# untitled.net
KiCad netlist of a schematic drawn in EAGLE
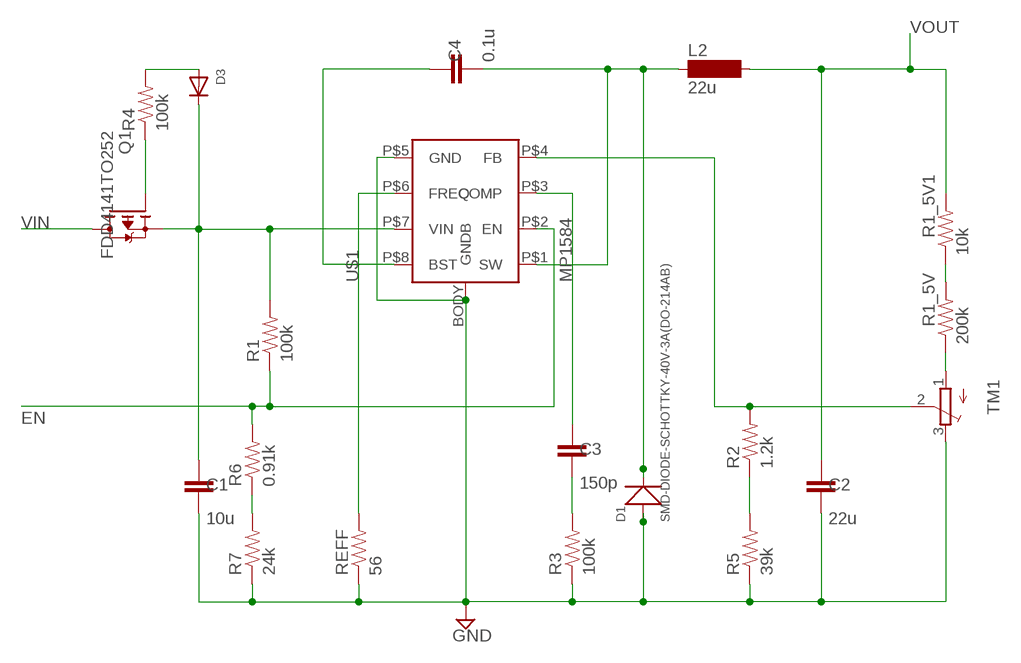
[diagram p0: schematic, sheet 1]

(export (version "E")
  (design (tool "Eeschema 10.0.6"))
  (components
    (comp (ref "C1")
      (value "10u")
      (footprint "eagle-import:0603-CAP")
      (libsource (lib "eagle-import") (part "CAP0603-CAP"))
    )
    (comp (ref "C2")
      (value "22u")
      (footprint "eagle-import:0603-CAP")
      (libsource (lib "eagle-import") (part "CAP0603-CAP"))
    )
    (comp (ref "C3")
      (value "150p")
      (footprint "eagle-import:0603-CAP")
      (libsource (lib "eagle-import") (part "CAP0603-CAP"))
    )
    (comp (ref "C4")
      (value "0.1u")
      (footprint "eagle-import:0603-CAP")
      (libsource (lib "eagle-import") (part "CAP0603-CAP"))
    )
    (comp (ref "D1")
      (value "SMD-DIODE-SCHOTTKY-40V-3A(DO-214AB)")
      (footprint "eagle-import:DO-214AB")
      (fields (field (name "MF") "Vishay") (field (name "MP") "SS34-E3/57T"))
      (libsource (lib "eagle-import") (part "SMD-DIODE-SCHOTTKY-40V-3A(DO-214AB)"))
    )
    (comp (ref "D3")
      (value "DIODESOD-523")
      (footprint "eagle-import:SOD-523")
      (libsource (lib "eagle-import") (part "DIODESOD-523"))
    )
    (comp (ref "L2")
      (value "22u")
      (footprint "eagle-import:SM-NE45")
      (libsource (lib "eagle-import") (part "SM-NE45"))
    )
    (comp (ref "Q1")
      (value "FDD4141TO252")
      (footprint "eagle-import:TO252")
      (libsource (lib "eagle-import") (part "FDD4141TO252"))
    )
    (comp (ref "R1")
      (value "100k")
      (footprint "eagle-import:0603-RES")
      (libsource (lib "eagle-import") (part "RESISTOR0603-RES"))
    )
    (comp (ref "R1_5V")
      (value "200k")
      (footprint "eagle-import:0603-RES")
      (libsource (lib "eagle-import") (part "RESISTOR0603-RES"))
    )
    (comp (ref "R1_5V1")
      (value "10k")
      (footprint "eagle-import:0603-RES")
      (libsource (lib "eagle-import") (part "RESISTOR0603-RES"))
    )
    (comp (ref "R2")
      (value "1.2k")
      (footprint "eagle-import:0603-RES")
      (libsource (lib "eagle-import") (part "RESISTOR0603-RES"))
    )
    (comp (ref "R3")
      (value "100k")
      (footprint "eagle-import:0603-RES")
      (libsource (lib "eagle-import") (part "RESISTOR0603"))
    )
    (comp (ref "R4")
      (value "100k")
      (footprint "eagle-import:0603-RES")
      (libsource (lib "eagle-import") (part "RESISTOR0603-RES"))
    )
    (comp (ref "R5")
      (value "39k")
      (footprint "eagle-import:0603-RES")
      (libsource (lib "eagle-import") (part "RESISTOR0603"))
    )
    (comp (ref "R6")
      (value "0.91k")
      (footprint "eagle-import:0603-RES")
      (libsource (lib "eagle-import") (part "RESISTOR0603"))
    )
    (comp (ref "R7")
      (value "24k")
      (footprint "eagle-import:0603-RES")
      (libsource (lib "eagle-import") (part "RESISTOR0603-RES"))
    )
    (comp (ref "REFF")
      (value "56")
      (footprint "eagle-import:0603-RES")
      (libsource (lib "eagle-import") (part "RESISTOR0603-RES"))
    )
    (comp (ref "TM1")
      (value "TRIMPOTTC33X")
      (footprint "eagle-import:TC33X")
      (libsource (lib "eagle-import") (part "TRIMPOTTC33X"))
    )
    (comp (ref "U$1")
      (value "MP1584")
      (footprint "eagle-import:MP")
      (libsource (lib "eagle-import") (part "MP1584"))
    )
  )
  (nets
    (net (code "1") (name "/EN") (class "Default")
      (node (ref "R1") (pin "1") (pinfunction "1_1") (pintype "passive"))
      (node (ref "R6") (pin "2") (pinfunction "2_2") (pintype "passive"))
      (node (ref "U$1") (pin "P$2") (pinfunction "EN_P$2") (pintype "bidirectional"))
    )
    (net (code "2") (name "/VIN") (class "Default")
      (node (ref "Q1") (pin "3") (pinfunction "D_3") (pintype "passive"))
    )
    (net (code "3") (name "/VOUT") (class "Default")
      (node (ref "C2") (pin "1") (pinfunction "1_1") (pintype "passive"))
      (node (ref "L2") (pin "2") (pinfunction "2_2") (pintype "passive"))
      (node (ref "R1_5V1") (pin "2") (pinfunction "2_2") (pintype "passive"))
    )
    (net (code "4") (name "GND") (class "Default")
      (node (ref "C1") (pin "2") (pinfunction "2_2") (pintype "passive"))
      (node (ref "C2") (pin "2") (pinfunction "2_2") (pintype "passive"))
      (node (ref "D1") (pin "1") (pinfunction "+_1") (pintype "passive"))
      (node (ref "R3") (pin "1") (pinfunction "1_1") (pintype "passive"))
      (node (ref "R5") (pin "1") (pinfunction "1_1") (pintype "passive"))
      (node (ref "R7") (pin "1") (pinfunction "1_1") (pintype "passive"))
      (node (ref "REFF") (pin "1") (pinfunction "1_1") (pintype "passive"))
      (node (ref "TM1") (pin "3") (pinfunction "E_3") (pintype "passive"))
      (node (ref "U$1") (pin "BODY") (pinfunction "GNDB_BODY") (pintype "bidirectional"))
      (node (ref "U$1") (pin "P$5") (pinfunction "GND_P$5") (pintype "bidirectional"))
    )
    (net (code "5") (name "Net-(C3-Pad2)") (class "Default")
      (node (ref "C3") (pin "2") (pinfunction "2_2") (pintype "passive"))
      (node (ref "R3") (pin "2") (pinfunction "2_2") (pintype "passive"))
    )
    (net (code "6") (name "Net-(D1--)") (class "Default")
      (node (ref "C4") (pin "2") (pinfunction "2_2") (pintype "passive"))
      (node (ref "D1") (pin "2") (pinfunction "-_2") (pintype "passive"))
      (node (ref "L2") (pin "1") (pinfunction "1_1") (pintype "passive"))
      (node (ref "U$1") (pin "P$1") (pinfunction "SW_P$1") (pintype "bidirectional"))
    )
    (net (code "7") (name "Net-(D3-C)") (class "Default")
      (node (ref "C1") (pin "1") (pinfunction "1_1") (pintype "passive"))
      (node (ref "D3") (pin "K") (pinfunction "C_K") (pintype "passive"))
      (node (ref "Q1") (pin "2") (pinfunction "S_2") (pintype "passive"))
      (node (ref "R1") (pin "2") (pinfunction "2_2") (pintype "passive"))
      (node (ref "U$1") (pin "P$7") (pinfunction "VIN_P$7") (pintype "bidirectional"))
    )
    (net (code "8") (name "Net-(D3-PadA)") (class "Default")
      (node (ref "D3") (pin "A") (pinfunction "A_A") (pintype "passive"))
      (node (ref "R4") (pin "2") (pinfunction "2_2") (pintype "passive"))
    )
    (net (code "9") (name "Net-(Q1-G)") (class "Default")
      (node (ref "Q1") (pin "1") (pinfunction "G_1") (pintype "passive"))
      (node (ref "R4") (pin "1") (pinfunction "1_1") (pintype "passive"))
    )
    (net (code "10") (name "Net-(R1_5V-Pad2)") (class "Default")
      (node (ref "R1_5V") (pin "2") (pinfunction "2_2") (pintype "passive"))
      (node (ref "R1_5V1") (pin "1") (pinfunction "1_1") (pintype "passive"))
    )
    (net (code "11") (name "Net-(R2-Pad1)") (class "Default")
      (node (ref "R2") (pin "1") (pinfunction "1_1") (pintype "passive"))
      (node (ref "R5") (pin "2") (pinfunction "2_2") (pintype "passive"))
    )
    (net (code "12") (name "Net-(R6-Pad1)") (class "Default")
      (node (ref "R6") (pin "1") (pinfunction "1_1") (pintype "passive"))
      (node (ref "R7") (pin "2") (pinfunction "2_2") (pintype "passive"))
    )
    (net (code "13") (name "Net-(TM1-A)") (class "Default")
      (node (ref "R1_5V") (pin "1") (pinfunction "1_1") (pintype "passive"))
      (node (ref "TM1") (pin "1") (pinfunction "A_1") (pintype "passive"))
    )
    (net (code "14") (name "Net-(TM1-S)") (class "Default")
      (node (ref "R2") (pin "2") (pinfunction "2_2") (pintype "passive"))
      (node (ref "TM1") (pin "2") (pinfunction "S_2") (pintype "passive"))
      (node (ref "U$1") (pin "P$4") (pinfunction "FB_P$4") (pintype "bidirectional"))
    )
    (net (code "15") (name "Net-(U$1-BST)") (class "Default")
      (node (ref "C4") (pin "1") (pinfunction "1_1") (pintype "passive"))
      (node (ref "U$1") (pin "P$8") (pinfunction "BST_P$8") (pintype "bidirectional"))
    )
    (net (code "16") (name "Net-(U$1-COMP)") (class "Default")
      (node (ref "C3") (pin "1") (pinfunction "1_1") (pintype "passive"))
      (node (ref "U$1") (pin "P$3") (pinfunction "COMP_P$3") (pintype "bidirectional"))
    )
    (net (code "17") (name "Net-(U$1-FREQ)") (class "Default")
      (node (ref "REFF") (pin "2") (pinfunction "2_2") (pintype "passive"))
      (node (ref "U$1") (pin "P$6") (pinfunction "FREQ_P$6") (pintype "bidirectional"))
    )
  )
)
